# PARAMETRIK.net
KiCad netlist of a schematic drawn in EAGLE
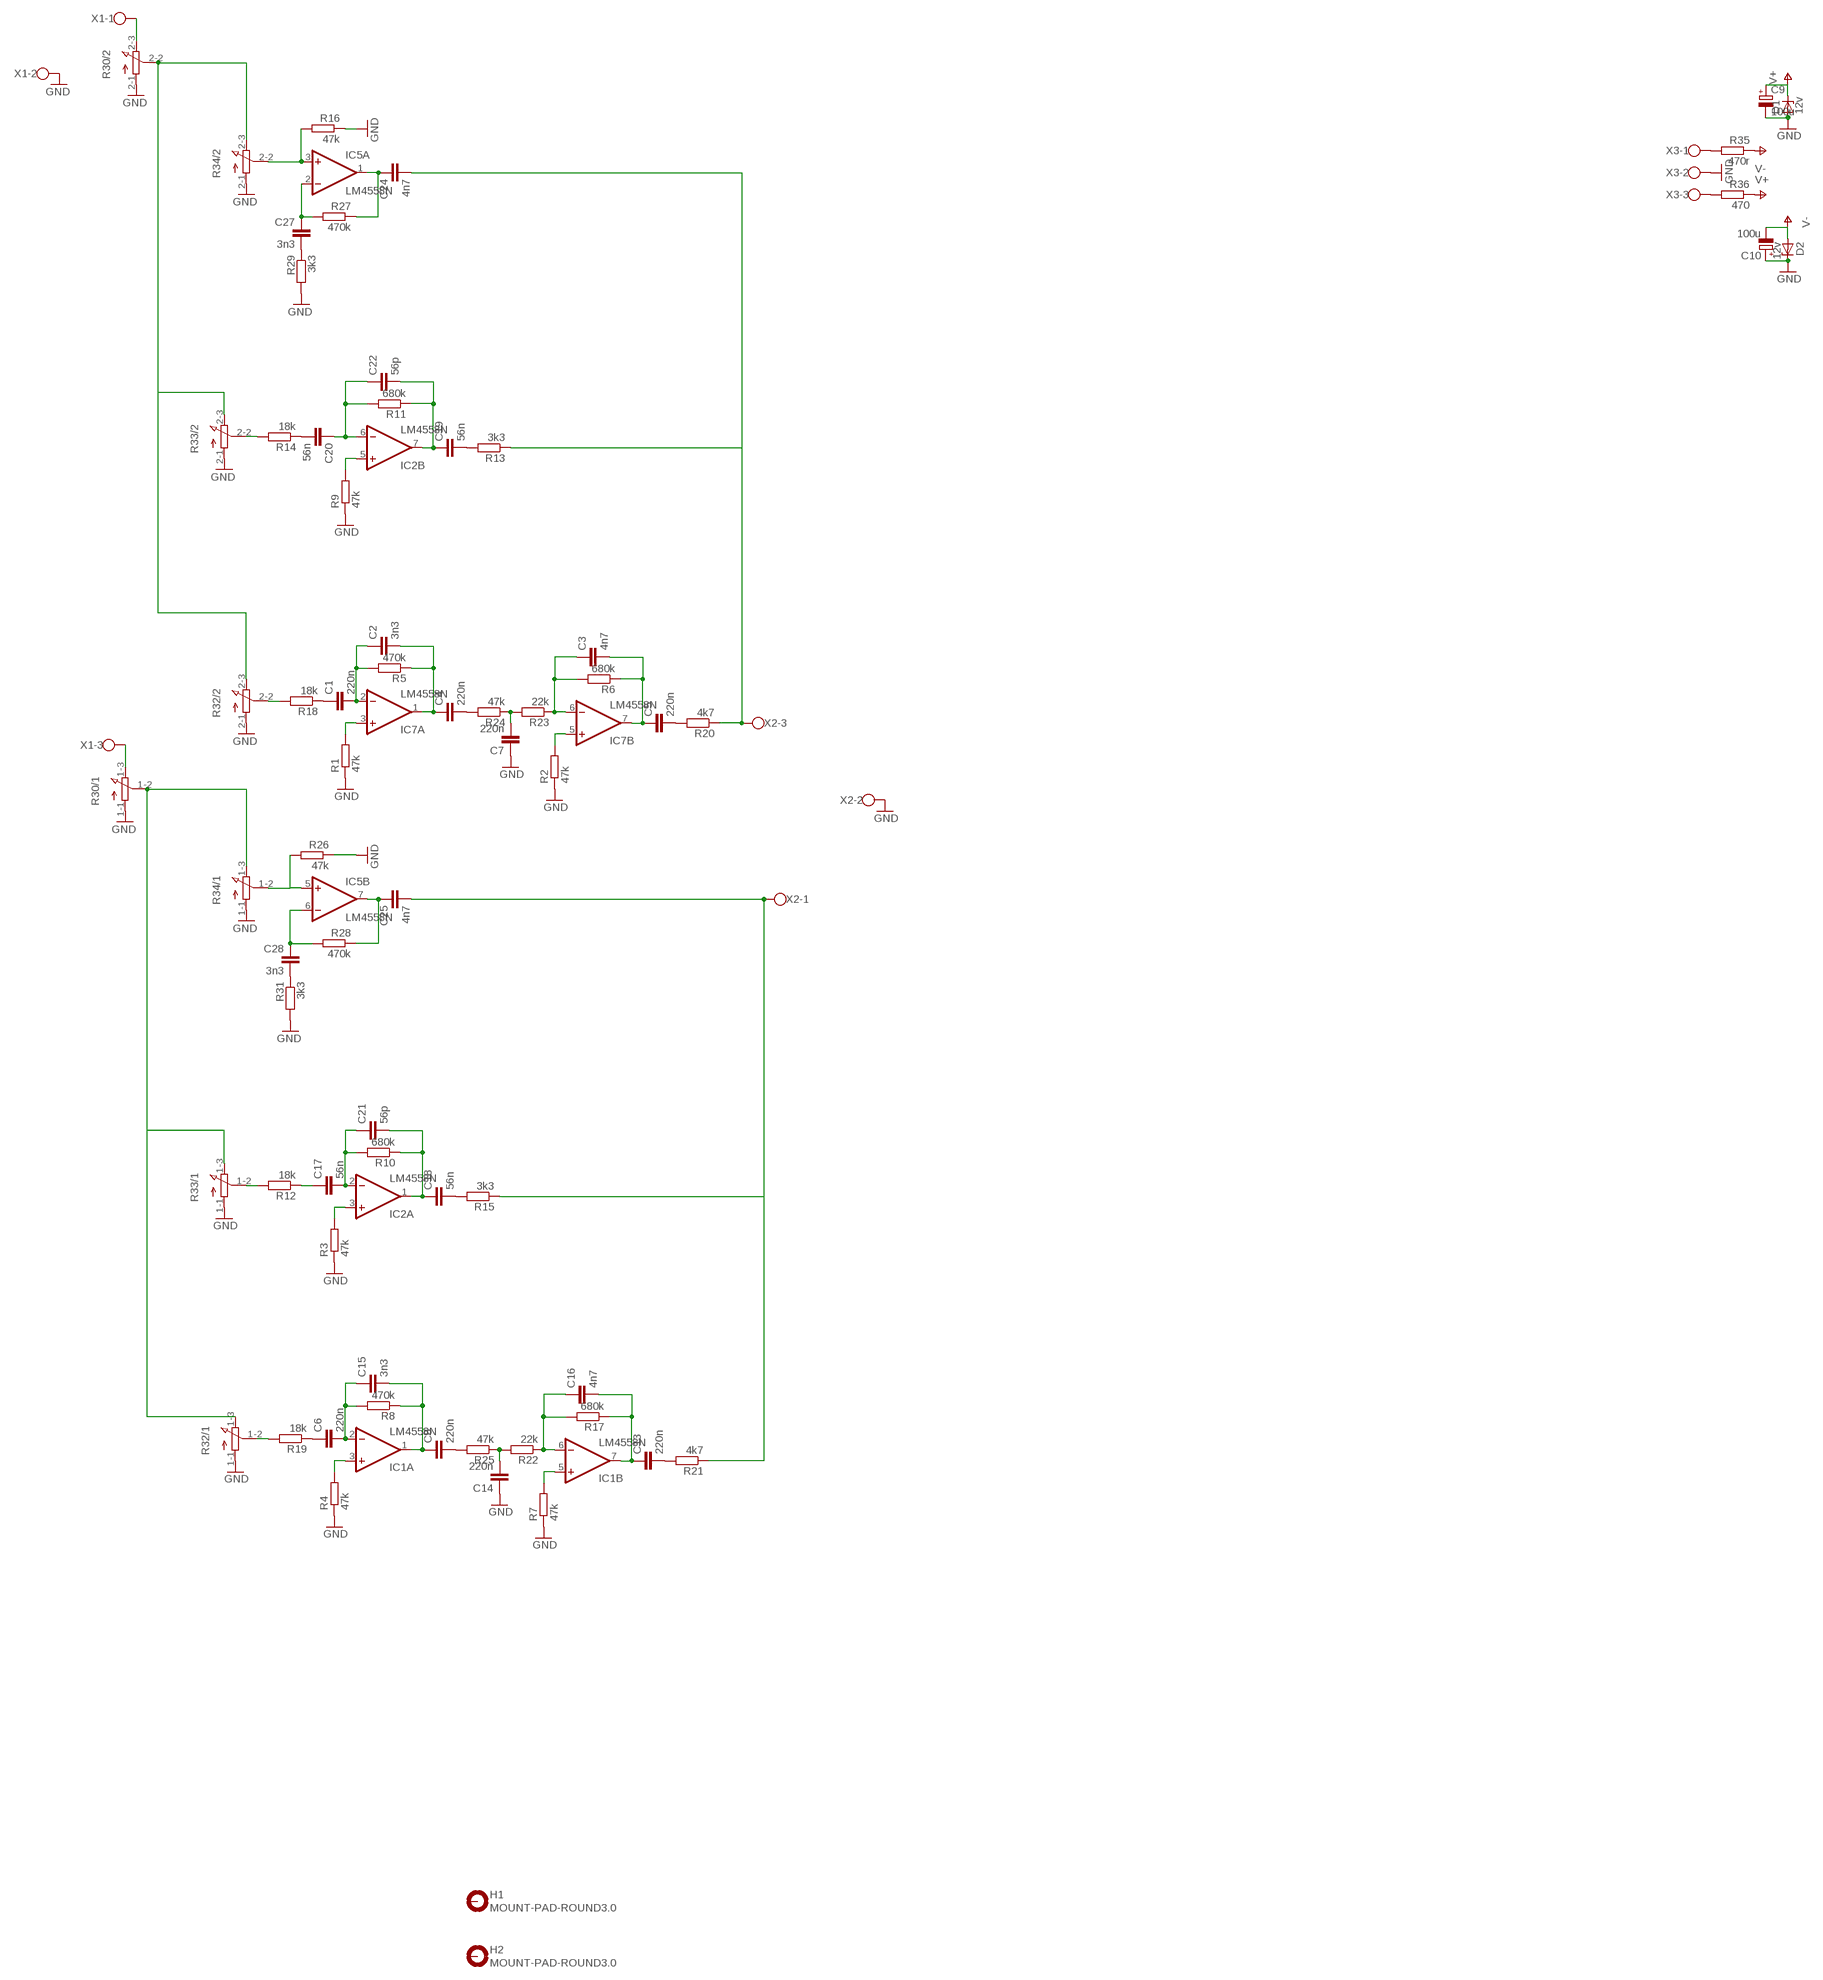
[diagram p0: schematic, sheet 1]

(export (version "E")
  (design (tool "Eeschema 10.0.6"))
  (components
    (comp (ref "C1")
      (value "220n")
      (footprint "eagle-import:C075-032X103")
      (libsource (lib "eagle-import") (part "C-EU075-032X103"))
    )
    (comp (ref "C2")
      (value "3n3")
      (footprint "eagle-import:C025-025X050")
      (libsource (lib "eagle-import") (part "C-EU025-025X050"))
    )
    (comp (ref "C3")
      (value "4n7")
      (footprint "eagle-import:C025-025X050")
      (libsource (lib "eagle-import") (part "C-EU025-025X050"))
    )
    (comp (ref "C4")
      (value "220n")
      (footprint "eagle-import:C075-032X103")
      (libsource (lib "eagle-import") (part "C-EU075-032X103"))
    )
    (comp (ref "C5")
      (value "220n")
      (footprint "eagle-import:C075-032X103")
      (libsource (lib "eagle-import") (part "C-EU075-032X103"))
    )
    (comp (ref "C6")
      (value "220n")
      (footprint "eagle-import:C075-032X103")
      (libsource (lib "eagle-import") (part "C-EU075-032X103"))
    )
    (comp (ref "C7")
      (value "220n")
      (footprint "eagle-import:C075-032X103")
      (libsource (lib "eagle-import") (part "C-EU075-032X103"))
    )
    (comp (ref "C8")
      (value "220n")
      (footprint "eagle-import:C075-032X103")
      (libsource (lib "eagle-import") (part "C-EU075-032X103"))
    )
    (comp (ref "C9")
      (value "100u")
      (footprint "eagle-import:E2,5-6")
      (libsource (lib "eagle-import") (part "CPOL-EUE2.5-6"))
    )
    (comp (ref "C10")
      (value "100u")
      (footprint "eagle-import:E2,5-6")
      (libsource (lib "eagle-import") (part "CPOL-EUE2.5-6"))
    )
    (comp (ref "C13")
      (value "220n")
      (footprint "eagle-import:C075-032X103")
      (libsource (lib "eagle-import") (part "C-EU075-032X103"))
    )
    (comp (ref "C14")
      (value "220n")
      (footprint "eagle-import:C075-032X103")
      (libsource (lib "eagle-import") (part "C-EU075-032X103"))
    )
    (comp (ref "C15")
      (value "3n3")
      (footprint "eagle-import:C025-025X050")
      (libsource (lib "eagle-import") (part "C-EU025-025X050"))
    )
    (comp (ref "C16")
      (value "4n7")
      (footprint "eagle-import:C025-025X050")
      (libsource (lib "eagle-import") (part "C-EU025-025X050"))
    )
    (comp (ref "C17")
      (value "56n")
      (footprint "eagle-import:C075-032X103")
      (libsource (lib "eagle-import") (part "C-EU075-032X103"))
    )
    (comp (ref "C18")
      (value "56n")
      (footprint "eagle-import:C075-032X103")
      (libsource (lib "eagle-import") (part "C-EU075-032X103"))
    )
    (comp (ref "C19")
      (value "56n")
      (footprint "eagle-import:C075-032X103")
      (libsource (lib "eagle-import") (part "C-EU075-032X103"))
    )
    (comp (ref "C20")
      (value "56n")
      (footprint "eagle-import:C075-032X103")
      (libsource (lib "eagle-import") (part "C-EU075-032X103"))
    )
    (comp (ref "C21")
      (value "56p")
      (footprint "eagle-import:C025-025X050")
      (libsource (lib "eagle-import") (part "C-EU025-025X050"))
    )
    (comp (ref "C22")
      (value "56p")
      (footprint "eagle-import:C025-025X050")
      (libsource (lib "eagle-import") (part "C-EU025-025X050"))
    )
    (comp (ref "C24")
      (value "4n7")
      (footprint "eagle-import:C075-032X103")
      (libsource (lib "eagle-import") (part "C-EU075-032X103"))
    )
    (comp (ref "C25")
      (value "4n7")
      (footprint "eagle-import:C075-032X103")
      (libsource (lib "eagle-import") (part "C-EU075-032X103"))
    )
    (comp (ref "C27")
      (value "3n3")
      (footprint "eagle-import:C025-025X050")
      (libsource (lib "eagle-import") (part "C-EU025-025X050"))
    )
    (comp (ref "C28")
      (value "3n3")
      (footprint "eagle-import:C025-025X050")
      (libsource (lib "eagle-import") (part "C-EU025-025X050"))
    )
    (comp (ref "D1")
      (value "12v")
      (footprint "eagle-import:DO35Z10")
      (libsource (lib "eagle-import") (part "1N821"))
    )
    (comp (ref "D2")
      (value "12v")
      (footprint "eagle-import:DO35Z10")
      (libsource (lib "eagle-import") (part "1N821"))
    )
    (comp (ref "H1")
      (value "MOUNT-PAD-ROUND3.0")
      (footprint "eagle-import:3,0-PAD")
      (libsource (lib "eagle-import") (part "MOUNT-PAD-ROUND3.0"))
    )
    (comp (ref "H2")
      (value "MOUNT-PAD-ROUND3.0")
      (footprint "eagle-import:3,0-PAD")
      (libsource (lib "eagle-import") (part "MOUNT-PAD-ROUND3.0"))
    )
    (comp (ref "IC1")
      (value "LM4558N")
      (footprint "eagle-import:DIL08")
      (libsource (lib "eagle-import") (part "4558NLM"))
    )
    (comp (ref "IC2")
      (value "LM4558N")
      (footprint "eagle-import:DIL08")
      (libsource (lib "eagle-import") (part "4558NLM"))
    )
    (comp (ref "IC5")
      (value "LM4558N")
      (footprint "eagle-import:DIL08")
      (libsource (lib "eagle-import") (part "4558NLM"))
    )
    (comp (ref "IC7")
      (value "LM4558N")
      (footprint "eagle-import:DIL08")
      (libsource (lib "eagle-import") (part "4558NLM"))
    )
    (comp (ref "R1")
      (value "47k")
      (footprint "eagle-import:0207_10")
      (libsource (lib "eagle-import") (part "R-EU_0207/10"))
    )
    (comp (ref "R2")
      (value "47k")
      (footprint "eagle-import:0207_10")
      (libsource (lib "eagle-import") (part "R-EU_0207/10"))
    )
    (comp (ref "R3")
      (value "47k")
      (footprint "eagle-import:0207_10")
      (libsource (lib "eagle-import") (part "R-EU_0207/10"))
    )
    (comp (ref "R4")
      (value "47k")
      (footprint "eagle-import:0207_10")
      (libsource (lib "eagle-import") (part "R-EU_0207/10"))
    )
    (comp (ref "R5")
      (value "470k")
      (footprint "eagle-import:0207_10")
      (libsource (lib "eagle-import") (part "R-EU_0207/10"))
    )
    (comp (ref "R6")
      (value "680k")
      (footprint "eagle-import:0207_10")
      (libsource (lib "eagle-import") (part "R-EU_0207/10"))
    )
    (comp (ref "R7")
      (value "47k")
      (footprint "eagle-import:0207_10")
      (libsource (lib "eagle-import") (part "R-EU_0207/10"))
    )
    (comp (ref "R8")
      (value "470k")
      (footprint "eagle-import:0207_10")
      (libsource (lib "eagle-import") (part "R-EU_0207/10"))
    )
    (comp (ref "R9")
      (value "47k")
      (footprint "eagle-import:0207_10")
      (libsource (lib "eagle-import") (part "R-EU_0207/10"))
    )
    (comp (ref "R10")
      (value "680k")
      (footprint "eagle-import:0207_10")
      (libsource (lib "eagle-import") (part "R-EU_0207/10"))
    )
    (comp (ref "R11")
      (value "680k")
      (footprint "eagle-import:0207_10")
      (libsource (lib "eagle-import") (part "R-EU_0207/10"))
    )
    (comp (ref "R12")
      (value "18k")
      (footprint "eagle-import:0207_10")
      (libsource (lib "eagle-import") (part "R-EU_0207/10"))
    )
    (comp (ref "R13")
      (value "3k3")
      (footprint "eagle-import:0207_10")
      (libsource (lib "eagle-import") (part "R-EU_0207/10"))
    )
    (comp (ref "R14")
      (value "18k")
      (footprint "eagle-import:0207_10")
      (libsource (lib "eagle-import") (part "R-EU_0207/10"))
    )
    (comp (ref "R15")
      (value "3k3")
      (footprint "eagle-import:0207_10")
      (libsource (lib "eagle-import") (part "R-EU_0207/10"))
    )
    (comp (ref "R16")
      (value "47k")
      (footprint "eagle-import:0207_10")
      (libsource (lib "eagle-import") (part "R-EU_0207/10"))
    )
    (comp (ref "R17")
      (value "680k")
      (footprint "eagle-import:0207_10")
      (libsource (lib "eagle-import") (part "R-EU_0207/10"))
    )
    (comp (ref "R18")
      (value "18k")
      (footprint "eagle-import:0207_10")
      (libsource (lib "eagle-import") (part "R-EU_0207/10"))
    )
    (comp (ref "R19")
      (value "18k")
      (footprint "eagle-import:0207_10")
      (libsource (lib "eagle-import") (part "R-EU_0207/10"))
    )
    (comp (ref "R20")
      (value "4k7")
      (footprint "eagle-import:0207_10")
      (libsource (lib "eagle-import") (part "R-EU_0207/10"))
    )
    (comp (ref "R21")
      (value "4k7")
      (footprint "eagle-import:0207_10")
      (libsource (lib "eagle-import") (part "R-EU_0207/10"))
    )
    (comp (ref "R22")
      (value "22k")
      (footprint "eagle-import:0207_10")
      (libsource (lib "eagle-import") (part "R-EU_0207/10"))
    )
    (comp (ref "R23")
      (value "22k")
      (footprint "eagle-import:0207_10")
      (libsource (lib "eagle-import") (part "R-EU_0207/10"))
    )
    (comp (ref "R24")
      (value "47k")
      (footprint "eagle-import:0207_10")
      (libsource (lib "eagle-import") (part "R-EU_0207/10"))
    )
    (comp (ref "R25")
      (value "47k")
      (footprint "eagle-import:0207_10")
      (libsource (lib "eagle-import") (part "R-EU_0207/10"))
    )
    (comp (ref "R26")
      (value "47k")
      (footprint "eagle-import:0207_10")
      (libsource (lib "eagle-import") (part "R-EU_0207/10"))
    )
    (comp (ref "R27")
      (value "470k")
      (footprint "eagle-import:0207_10")
      (libsource (lib "eagle-import") (part "R-EU_0207/10"))
    )
    (comp (ref "R28")
      (value "470k")
      (footprint "eagle-import:0207_10")
      (libsource (lib "eagle-import") (part "R-EU_0207/10"))
    )
    (comp (ref "R29")
      (value "3k3")
      (footprint "eagle-import:0207_10")
      (libsource (lib "eagle-import") (part "R-EU_0207/10"))
    )
    (comp (ref "R30")
      (value "3RP/1610G")
      (footprint "eagle-import:3RP_1610G")
      (libsource (lib "eagle-import") (part "3RP/1610G"))
    )
    (comp (ref "R31")
      (value "3k3")
      (footprint "eagle-import:0207_10")
      (libsource (lib "eagle-import") (part "R-EU_0207/10"))
    )
    (comp (ref "R32")
      (value "3RP/1610G")
      (footprint "eagle-import:3RP_1610G")
      (libsource (lib "eagle-import") (part "3RP/1610G"))
    )
    (comp (ref "R33")
      (value "3RP/1610G")
      (footprint "eagle-import:3RP_1610G")
      (libsource (lib "eagle-import") (part "3RP/1610G"))
    )
    (comp (ref "R34")
      (value "3RP/1610G")
      (footprint "eagle-import:3RP_1610G")
      (libsource (lib "eagle-import") (part "3RP/1610G"))
    )
    (comp (ref "R35")
      (value "470r")
      (footprint "eagle-import:0207_10")
      (libsource (lib "eagle-import") (part "R-EU_0207/10"))
    )
    (comp (ref "R36")
      (value "470")
      (footprint "eagle-import:0207_10")
      (libsource (lib "eagle-import") (part "R-EU_0207/10"))
    )
    (comp (ref "X1")
      (value "W237-103")
      (footprint "eagle-import:W237-103")
      (fields (field (name "MPN") "237-103"))
      (libsource (lib "eagle-import") (part "W237-103"))
    )
    (comp (ref "X2")
      (value "W237-103")
      (footprint "eagle-import:W237-103")
      (fields (field (name "MPN") "237-103"))
      (libsource (lib "eagle-import") (part "W237-103"))
    )
    (comp (ref "X3")
      (value "W237-103")
      (footprint "eagle-import:W237-103")
      (fields (field (name "MPN") "237-103"))
      (libsource (lib "eagle-import") (part "W237-103"))
    )
  )
  (nets
    (net (code "1") (name "GND") (class "Default")
      (node (ref "C10") (pin "+") (pinfunction "+_+") (pintype "passive"))
      (node (ref "C14") (pin "1") (pinfunction "1_1") (pintype "passive"))
      (node (ref "C7") (pin "1") (pinfunction "1_1") (pintype "passive"))
      (node (ref "C9") (pin "-") (pinfunction "-_-") (pintype "passive"))
      (node (ref "D1") (pin "A") (pinfunction "A_A") (pintype "passive"))
      (node (ref "D2") (pin "C") (pinfunction "C_C") (pintype "passive"))
      (node (ref "R1") (pin "1") (pinfunction "1_1") (pintype "passive"))
      (node (ref "R16") (pin "1") (pinfunction "1_1") (pintype "passive"))
      (node (ref "R2") (pin "1") (pinfunction "1_1") (pintype "passive"))
      (node (ref "R26") (pin "1") (pinfunction "1_1") (pintype "passive"))
      (node (ref "R29") (pin "2") (pinfunction "2_2") (pintype "passive"))
      (node (ref "R3") (pin "1") (pinfunction "1_1") (pintype "passive"))
      (node (ref "R30") (pin "1-1") (pinfunction "A_1-1") (pintype "passive"))
      (node (ref "R30") (pin "2-1") (pinfunction "A_2-1") (pintype "passive"))
      (node (ref "R31") (pin "2") (pinfunction "2_2") (pintype "passive"))
      (node (ref "R32") (pin "1-1") (pinfunction "A_1-1") (pintype "passive"))
      (node (ref "R32") (pin "2-1") (pinfunction "A_2-1") (pintype "passive"))
      (node (ref "R33") (pin "1-1") (pinfunction "A_1-1") (pintype "passive"))
      (node (ref "R33") (pin "2-1") (pinfunction "A_2-1") (pintype "passive"))
      (node (ref "R34") (pin "1-1") (pinfunction "A_1-1") (pintype "passive"))
      (node (ref "R34") (pin "2-1") (pinfunction "A_2-1") (pintype "passive"))
      (node (ref "R4") (pin "1") (pinfunction "1_1") (pintype "passive"))
      (node (ref "R7") (pin "1") (pinfunction "1_1") (pintype "passive"))
      (node (ref "R9") (pin "1") (pinfunction "1_1") (pintype "passive"))
      (node (ref "X1") (pin "2") (pinfunction "KL_2") (pintype "passive"))
      (node (ref "X2") (pin "2") (pinfunction "KL_2") (pintype "passive"))
      (node (ref "X3") (pin "2") (pinfunction "KL_2") (pintype "passive"))
    )
    (net (code "2") (name "Net-(C1-Pad1)") (class "Default")
      (node (ref "C1") (pin "1") (pinfunction "1_1") (pintype "passive"))
      (node (ref "R18") (pin "1") (pinfunction "1_1") (pintype "passive"))
    )
    (net (code "3") (name "Net-(C4-Pad2)") (class "Default")
      (node (ref "C4") (pin "2") (pinfunction "2_2") (pintype "passive"))
      (node (ref "R24") (pin "2") (pinfunction "2_2") (pintype "passive"))
    )
    (net (code "4") (name "Net-(C5-Pad2)") (class "Default")
      (node (ref "C5") (pin "2") (pinfunction "2_2") (pintype "passive"))
      (node (ref "R20") (pin "2") (pinfunction "2_2") (pintype "passive"))
    )
    (net (code "5") (name "Net-(C6-Pad1)") (class "Default")
      (node (ref "C6") (pin "1") (pinfunction "1_1") (pintype "passive"))
      (node (ref "R19") (pin "1") (pinfunction "1_1") (pintype "passive"))
    )
    (net (code "6") (name "Net-(C7-Pad2)") (class "Default")
      (node (ref "C7") (pin "2") (pinfunction "2_2") (pintype "passive"))
      (node (ref "R23") (pin "2") (pinfunction "2_2") (pintype "passive"))
      (node (ref "R24") (pin "1") (pinfunction "1_1") (pintype "passive"))
    )
    (net (code "7") (name "Net-(C8-Pad2)") (class "Default")
      (node (ref "C8") (pin "2") (pinfunction "2_2") (pintype "passive"))
      (node (ref "R25") (pin "2") (pinfunction "2_2") (pintype "passive"))
    )
    (net (code "8") (name "Net-(C13-Pad2)") (class "Default")
      (node (ref "C13") (pin "2") (pinfunction "2_2") (pintype "passive"))
      (node (ref "R21") (pin "2") (pinfunction "2_2") (pintype "passive"))
    )
    (net (code "9") (name "Net-(C14-Pad2)") (class "Default")
      (node (ref "C14") (pin "2") (pinfunction "2_2") (pintype "passive"))
      (node (ref "R22") (pin "2") (pinfunction "2_2") (pintype "passive"))
      (node (ref "R25") (pin "1") (pinfunction "1_1") (pintype "passive"))
    )
    (net (code "10") (name "Net-(C17-Pad1)") (class "Default")
      (node (ref "C17") (pin "1") (pinfunction "1_1") (pintype "passive"))
      (node (ref "R12") (pin "1") (pinfunction "1_1") (pintype "passive"))
    )
    (net (code "11") (name "Net-(C18-Pad2)") (class "Default")
      (node (ref "C18") (pin "2") (pinfunction "2_2") (pintype "passive"))
      (node (ref "R15") (pin "2") (pinfunction "2_2") (pintype "passive"))
    )
    (net (code "12") (name "Net-(C19-Pad2)") (class "Default")
      (node (ref "C19") (pin "2") (pinfunction "2_2") (pintype "passive"))
      (node (ref "R13") (pin "2") (pinfunction "2_2") (pintype "passive"))
    )
    (net (code "13") (name "Net-(C20-Pad2)") (class "Default")
      (node (ref "C20") (pin "2") (pinfunction "2_2") (pintype "passive"))
      (node (ref "R14") (pin "1") (pinfunction "1_1") (pintype "passive"))
    )
    (net (code "14") (name "Net-(C27-Pad2)") (class "Default")
      (node (ref "C27") (pin "2") (pinfunction "2_2") (pintype "passive"))
      (node (ref "R29") (pin "1") (pinfunction "1_1") (pintype "passive"))
    )
    (net (code "15") (name "Net-(C28-Pad2)") (class "Default")
      (node (ref "C28") (pin "2") (pinfunction "2_2") (pintype "passive"))
      (node (ref "R31") (pin "1") (pinfunction "1_1") (pintype "passive"))
    )
    (net (code "16") (name "Net-(IC1A-+IN)") (class "Default")
      (node (ref "IC1") (pin "3") (pinfunction "+IN_3") (pintype "input"))
      (node (ref "R4") (pin "2") (pinfunction "2_2") (pintype "passive"))
    )
    (net (code "17") (name "Net-(IC1A--IN)") (class "Default")
      (node (ref "C15") (pin "1") (pinfunction "1_1") (pintype "passive"))
      (node (ref "C6") (pin "2") (pinfunction "2_2") (pintype "passive"))
      (node (ref "IC1") (pin "2") (pinfunction "-IN_2") (pintype "input"))
      (node (ref "R8") (pin "2") (pinfunction "2_2") (pintype "passive"))
    )
    (net (code "18") (name "Net-(IC1A-OUT)") (class "Default")
      (node (ref "C15") (pin "2") (pinfunction "2_2") (pintype "passive"))
      (node (ref "C8") (pin "1") (pinfunction "1_1") (pintype "passive"))
      (node (ref "IC1") (pin "1") (pinfunction "OUT_1") (pintype "output"))
      (node (ref "R8") (pin "1") (pinfunction "1_1") (pintype "passive"))
    )
    (net (code "19") (name "Net-(IC1B-+IN)") (class "Default")
      (node (ref "IC1") (pin "5") (pinfunction "+IN_5") (pintype "input"))
      (node (ref "R7") (pin "2") (pinfunction "2_2") (pintype "passive"))
    )
    (net (code "20") (name "Net-(IC1B--IN)") (class "Default")
      (node (ref "C16") (pin "1") (pinfunction "1_1") (pintype "passive"))
      (node (ref "IC1") (pin "6") (pinfunction "-IN_6") (pintype "input"))
      (node (ref "R17") (pin "2") (pinfunction "2_2") (pintype "passive"))
      (node (ref "R22") (pin "1") (pinfunction "1_1") (pintype "passive"))
    )
    (net (code "21") (name "Net-(IC1B-OUT)") (class "Default")
      (node (ref "C13") (pin "1") (pinfunction "1_1") (pintype "passive"))
      (node (ref "C16") (pin "2") (pinfunction "2_2") (pintype "passive"))
      (node (ref "IC1") (pin "7") (pinfunction "OUT_7") (pintype "output"))
      (node (ref "R17") (pin "1") (pinfunction "1_1") (pintype "passive"))
    )
    (net (code "22") (name "Net-(IC2A-+IN)") (class "Default")
      (node (ref "IC2") (pin "3") (pinfunction "+IN_3") (pintype "input"))
      (node (ref "R3") (pin "2") (pinfunction "2_2") (pintype "passive"))
    )
    (net (code "23") (name "Net-(IC2A--IN)") (class "Default")
      (node (ref "C17") (pin "2") (pinfunction "2_2") (pintype "passive"))
      (node (ref "C21") (pin "1") (pinfunction "1_1") (pintype "passive"))
      (node (ref "IC2") (pin "2") (pinfunction "-IN_2") (pintype "input"))
      (node (ref "R10") (pin "2") (pinfunction "2_2") (pintype "passive"))
    )
    (net (code "24") (name "Net-(IC2A-OUT)") (class "Default")
      (node (ref "C18") (pin "1") (pinfunction "1_1") (pintype "passive"))
      (node (ref "C21") (pin "2") (pinfunction "2_2") (pintype "passive"))
      (node (ref "IC2") (pin "1") (pinfunction "OUT_1") (pintype "output"))
      (node (ref "R10") (pin "1") (pinfunction "1_1") (pintype "passive"))
    )
    (net (code "25") (name "Net-(IC2B-+IN)") (class "Default")
      (node (ref "IC2") (pin "5") (pinfunction "+IN_5") (pintype "input"))
      (node (ref "R9") (pin "2") (pinfunction "2_2") (pintype "passive"))
    )
    (net (code "26") (name "Net-(IC2B--IN)") (class "Default")
      (node (ref "C20") (pin "1") (pinfunction "1_1") (pintype "passive"))
      (node (ref "C22") (pin "1") (pinfunction "1_1") (pintype "passive"))
      (node (ref "IC2") (pin "6") (pinfunction "-IN_6") (pintype "input"))
      (node (ref "R11") (pin "2") (pinfunction "2_2") (pintype "passive"))
    )
    (net (code "27") (name "Net-(IC2B-OUT)") (class "Default")
      (node (ref "C19") (pin "1") (pinfunction "1_1") (pintype "passive"))
      (node (ref "C22") (pin "2") (pinfunction "2_2") (pintype "passive"))
      (node (ref "IC2") (pin "7") (pinfunction "OUT_7") (pintype "output"))
      (node (ref "R11") (pin "1") (pinfunction "1_1") (pintype "passive"))
    )
    (net (code "28") (name "Net-(IC5A-+IN)") (class "Default")
      (node (ref "IC5") (pin "3") (pinfunction "+IN_3") (pintype "input"))
      (node (ref "R16") (pin "2") (pinfunction "2_2") (pintype "passive"))
      (node (ref "R34") (pin "2-2") (pinfunction "S_2-2") (pintype "passive"))
    )
    (net (code "29") (name "Net-(IC5A--IN)") (class "Default")
      (node (ref "C27") (pin "1") (pinfunction "1_1") (pintype "passive"))
      (node (ref "IC5") (pin "2") (pinfunction "-IN_2") (pintype "input"))
      (node (ref "R27") (pin "2") (pinfunction "2_2") (pintype "passive"))
    )
    (net (code "30") (name "Net-(IC5A-OUT)") (class "Default")
      (node (ref "C24") (pin "1") (pinfunction "1_1") (pintype "passive"))
      (node (ref "IC5") (pin "1") (pinfunction "OUT_1") (pintype "output"))
      (node (ref "R27") (pin "1") (pinfunction "1_1") (pintype "passive"))
    )
    (net (code "31") (name "Net-(IC5B-+IN)") (class "Default")
      (node (ref "IC5") (pin "5") (pinfunction "+IN_5") (pintype "input"))
      (node (ref "R26") (pin "2") (pinfunction "2_2") (pintype "passive"))
      (node (ref "R34") (pin "1-2") (pinfunction "S_1-2") (pintype "passive"))
    )
    (net (code "32") (name "Net-(IC5B--IN)") (class "Default")
      (node (ref "C28") (pin "1") (pinfunction "1_1") (pintype "passive"))
      (node (ref "IC5") (pin "6") (pinfunction "-IN_6") (pintype "input"))
      (node (ref "R28") (pin "2") (pinfunction "2_2") (pintype "passive"))
    )
    (net (code "33") (name "Net-(IC5B-OUT)") (class "Default")
      (node (ref "C25") (pin "1") (pinfunction "1_1") (pintype "passive"))
      (node (ref "IC5") (pin "7") (pinfunction "OUT_7") (pintype "output"))
      (node (ref "R28") (pin "1") (pinfunction "1_1") (pintype "passive"))
    )
    (net (code "34") (name "Net-(IC7A-+IN)") (class "Default")
      (node (ref "IC7") (pin "3") (pinfunction "+IN_3") (pintype "input"))
      (node (ref "R1") (pin "2") (pinfunction "2_2") (pintype "passive"))
    )
    (net (code "35") (name "Net-(IC7A--IN)") (class "Default")
      (node (ref "C1") (pin "2") (pinfunction "2_2") (pintype "passive"))
      (node (ref "C2") (pin "1") (pinfunction "1_1") (pintype "passive"))
      (node (ref "IC7") (pin "2") (pinfunction "-IN_2") (pintype "input"))
      (node (ref "R5") (pin "2") (pinfunction "2_2") (pintype "passive"))
    )
    (net (code "36") (name "Net-(IC7A-OUT)") (class "Default")
      (node (ref "C2") (pin "2") (pinfunction "2_2") (pintype "passive"))
      (node (ref "C4") (pin "1") (pinfunction "1_1") (pintype "passive"))
      (node (ref "IC7") (pin "1") (pinfunction "OUT_1") (pintype "output"))
      (node (ref "R5") (pin "1") (pinfunction "1_1") (pintype "passive"))
    )
    (net (code "37") (name "Net-(IC7B-+IN)") (class "Default")
      (node (ref "IC7") (pin "5") (pinfunction "+IN_5") (pintype "input"))
      (node (ref "R2") (pin "2") (pinfunction "2_2") (pintype "passive"))
    )
    (net (code "38") (name "Net-(IC7B--IN)") (class "Default")
      (node (ref "C3") (pin "1") (pinfunction "1_1") (pintype "passive"))
      (node (ref "IC7") (pin "6") (pinfunction "-IN_6") (pintype "input"))
      (node (ref "R23") (pin "1") (pinfunction "1_1") (pintype "passive"))
      (node (ref "R6") (pin "2") (pinfunction "2_2") (pintype "passive"))
    )
    (net (code "39") (name "Net-(IC7B-OUT)") (class "Default")
      (node (ref "C3") (pin "2") (pinfunction "2_2") (pintype "passive"))
      (node (ref "C5") (pin "1") (pinfunction "1_1") (pintype "passive"))
      (node (ref "IC7") (pin "7") (pinfunction "OUT_7") (pintype "output"))
      (node (ref "R6") (pin "1") (pinfunction "1_1") (pintype "passive"))
    )
    (net (code "40") (name "Net-(R30A-E)") (class "Default")
      (node (ref "R30") (pin "1-3") (pinfunction "E_1-3") (pintype "passive"))
      (node (ref "X1") (pin "3") (pinfunction "KL_3") (pintype "passive"))
    )
    (net (code "41") (name "Net-(R30A-S)") (class "Default")
      (node (ref "R30") (pin "1-2") (pinfunction "S_1-2") (pintype "passive"))
      (node (ref "R32") (pin "1-3") (pinfunction "E_1-3") (pintype "passive"))
      (node (ref "R33") (pin "1-3") (pinfunction "E_1-3") (pintype "passive"))
      (node (ref "R34") (pin "1-3") (pinfunction "E_1-3") (pintype "passive"))
    )
    (net (code "42") (name "Net-(R30B-E)") (class "Default")
      (node (ref "R30") (pin "2-3") (pinfunction "E_2-3") (pintype "passive"))
      (node (ref "X1") (pin "1") (pinfunction "KL_1") (pintype "passive"))
    )
    (net (code "43") (name "Net-(R30B-S)") (class "Default")
      (node (ref "R30") (pin "2-2") (pinfunction "S_2-2") (pintype "passive"))
      (node (ref "R32") (pin "2-3") (pinfunction "E_2-3") (pintype "passive"))
      (node (ref "R33") (pin "2-3") (pinfunction "E_2-3") (pintype "passive"))
      (node (ref "R34") (pin "2-3") (pinfunction "E_2-3") (pintype "passive"))
    )
    (net (code "44") (name "Net-(R32A-S)") (class "Default")
      (node (ref "R19") (pin "2") (pinfunction "2_2") (pintype "passive"))
      (node (ref "R32") (pin "1-2") (pinfunction "S_1-2") (pintype "passive"))
    )
    (net (code "45") (name "Net-(R32B-S)") (class "Default")
      (node (ref "R18") (pin "2") (pinfunction "2_2") (pintype "passive"))
      (node (ref "R32") (pin "2-2") (pinfunction "S_2-2") (pintype "passive"))
    )
    (net (code "46") (name "Net-(R33A-S)") (class "Default")
      (node (ref "R12") (pin "2") (pinfunction "2_2") (pintype "passive"))
      (node (ref "R33") (pin "1-2") (pinfunction "S_1-2") (pintype "passive"))
    )
    (net (code "47") (name "Net-(R33B-S)") (class "Default")
      (node (ref "R14") (pin "2") (pinfunction "2_2") (pintype "passive"))
      (node (ref "R33") (pin "2-2") (pinfunction "S_2-2") (pintype "passive"))
    )
    (net (code "48") (name "Net-(X2A-KL)") (class "Default")
      (node (ref "C25") (pin "2") (pinfunction "2_2") (pintype "passive"))
      (node (ref "R15") (pin "1") (pinfunction "1_1") (pintype "passive"))
      (node (ref "R21") (pin "1") (pinfunction "1_1") (pintype "passive"))
      (node (ref "X2") (pin "1") (pinfunction "KL_1") (pintype "passive"))
    )
    (net (code "49") (name "Net-(X2C-KL)") (class "Default")
      (node (ref "C24") (pin "2") (pinfunction "2_2") (pintype "passive"))
      (node (ref "R13") (pin "1") (pinfunction "1_1") (pintype "passive"))
      (node (ref "R20") (pin "1") (pinfunction "1_1") (pintype "passive"))
      (node (ref "X2") (pin "3") (pinfunction "KL_3") (pintype "passive"))
    )
    (net (code "50") (name "Net-(X3A-KL)") (class "Default")
      (node (ref "R35") (pin "2") (pinfunction "2_2") (pintype "passive"))
      (node (ref "X3") (pin "1") (pinfunction "KL_1") (pintype "passive"))
    )
    (net (code "51") (name "Net-(X3C-KL)") (class "Default")
      (node (ref "R36") (pin "2") (pinfunction "2_2") (pintype "passive"))
      (node (ref "X3") (pin "3") (pinfunction "KL_3") (pintype "passive"))
    )
    (net (code "52") (name "V+") (class "Default")
      (node (ref "C9") (pin "+") (pinfunction "+_+") (pintype "passive"))
      (node (ref "D1") (pin "C") (pinfunction "C_C") (pintype "passive"))
      (node (ref "R36") (pin "1") (pinfunction "1_1") (pintype "passive"))
    )
    (net (code "53") (name "V-") (class "Default")
      (node (ref "C10") (pin "-") (pinfunction "-_-") (pintype "passive"))
      (node (ref "D2") (pin "A") (pinfunction "A_A") (pintype "passive"))
      (node (ref "R35") (pin "1") (pinfunction "1_1") (pintype "passive"))
    )
    (net (code "54") (name "unconnected-(H1-MOUNT-PadB3,0)") (class "Default")
      (node (ref "H1") (pin "B3,0") (pinfunction "MOUNT_B3,0") (pintype "passive"))
    )
    (net (code "55") (name "unconnected-(H2-MOUNT-PadB3,0)") (class "Default")
      (node (ref "H2") (pin "B3,0") (pinfunction "MOUNT_B3,0") (pintype "passive"))
    )
  )
)
